# design.net
KiCad netlist of a schematic drawn in Altium Designer
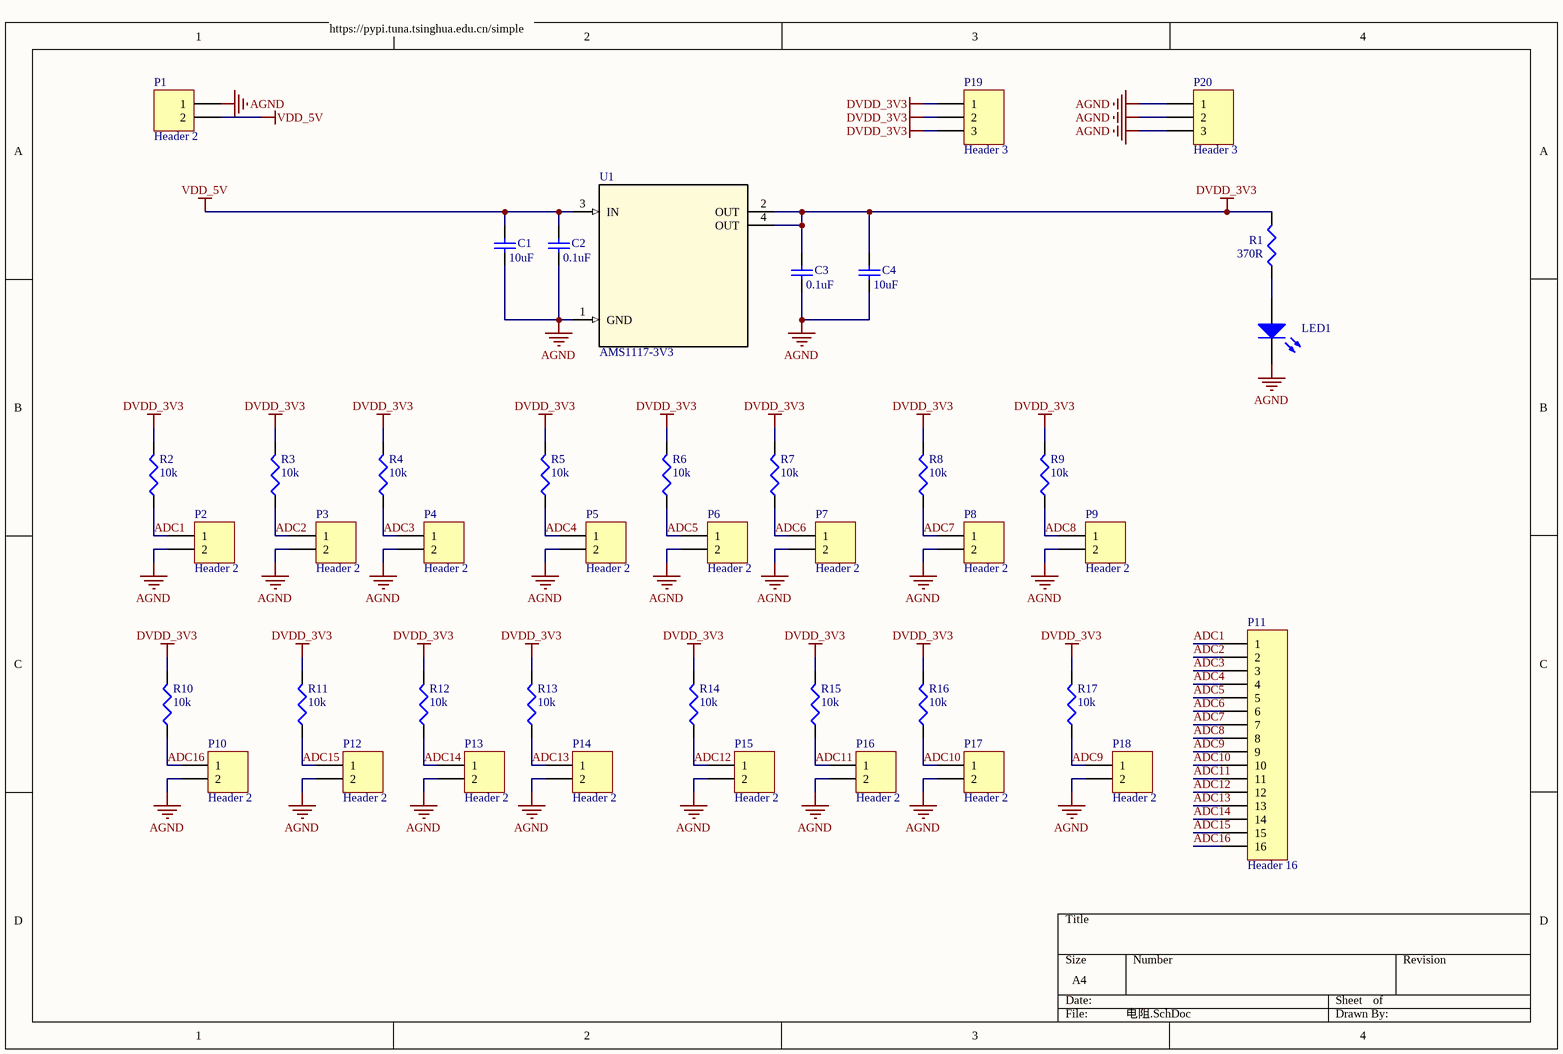
[diagram p0: 电阻.SchDoc]

(export (version "E")
  (design (tool "Eeschema 10.0.6"))
  (components
    (comp (ref "C1")
      (value "10uF")
      (footprint "C-0603")
      (description "Capacitor (Semiconductor SIM Model)")
      (fields (field (name "PUBLISHER") "Altium Limited"))
      (libsource (lib "Miscellaneous Devices") (part "Cap Semi"))
    )
    (comp (ref "C2")
      (value "0.1uF")
      (footprint "C-0603")
      (description "Capacitor (Semiconductor SIM Model)")
      (fields (field (name "PUBLISHER") "Altium Limited"))
      (libsource (lib "Miscellaneous Devices") (part "Cap Semi"))
    )
    (comp (ref "C3")
      (value "0.1uF")
      (footprint "C-0603")
      (description "Capacitor (Semiconductor SIM Model)")
      (fields (field (name "PUBLISHER") "Altium Limited"))
      (libsource (lib "Miscellaneous Devices") (part "Cap Semi"))
    )
    (comp (ref "C4")
      (value "10uF")
      (footprint "C-0603")
      (description "Capacitor (Semiconductor SIM Model)")
      (fields (field (name "PUBLISHER") "Altium Limited"))
      (libsource (lib "Miscellaneous Devices") (part "Cap Semi"))
    )
    (comp (ref "LED1")
      (value "~")
      (footprint "CLED1608-0603")
      (description "Typical Chip LED")
      (fields (field (name "PUBLISHER") "Altium Limited"))
      (libsource (lib "EButterflyIntegratedLibrary") (part "LED Chip"))
    )
    (comp (ref "P1")
      (value "Header 2")
      (footprint "XH2.54-LI-2P")
      (description "Header, 2-Pin")
      (fields (field (name "PUBLISHER") "Altium Limited"))
      (libsource (lib "") (part "Header 2_1"))
    )
    (comp (ref "P2")
      (value "Header 2")
      (footprint "XH2.0_2p")
      (description "Header, 2-Pin")
      (fields (field (name "PUBLISHER") "Altium Limited"))
      (libsource (lib "Miscellaneous Connectors") (part "Header 2"))
    )
    (comp (ref "P3")
      (value "Header 2")
      (footprint "XH2.0_2p")
      (description "Header, 2-Pin")
      (fields (field (name "PUBLISHER") "Altium Limited"))
      (libsource (lib "Miscellaneous Connectors") (part "Header 2"))
    )
    (comp (ref "P4")
      (value "Header 2")
      (footprint "XH2.0_2p")
      (description "Header, 2-Pin")
      (fields (field (name "PUBLISHER") "Altium Limited"))
      (libsource (lib "Miscellaneous Connectors") (part "Header 2"))
    )
    (comp (ref "P5")
      (value "Header 2")
      (footprint "XH2.0_2p")
      (description "Header, 2-Pin")
      (fields (field (name "PUBLISHER") "Altium Limited"))
      (libsource (lib "Miscellaneous Connectors") (part "Header 2"))
    )
    (comp (ref "P6")
      (value "Header 2")
      (footprint "XH2.0_2p")
      (description "Header, 2-Pin")
      (fields (field (name "PUBLISHER") "Altium Limited"))
      (libsource (lib "Miscellaneous Connectors") (part "Header 2"))
    )
    (comp (ref "P7")
      (value "Header 2")
      (footprint "XH2.0_2p")
      (description "Header, 2-Pin")
      (fields (field (name "PUBLISHER") "Altium Limited"))
      (libsource (lib "Miscellaneous Connectors") (part "Header 2"))
    )
    (comp (ref "P8")
      (value "Header 2")
      (footprint "XH2.0_2p")
      (description "Header, 2-Pin")
      (fields (field (name "PUBLISHER") "Altium Limited"))
      (libsource (lib "Miscellaneous Connectors") (part "Header 2"))
    )
    (comp (ref "P9")
      (value "Header 2")
      (footprint "XH2.0_2p")
      (description "Header, 2-Pin")
      (fields (field (name "PUBLISHER") "Altium Limited"))
      (libsource (lib "Miscellaneous Connectors") (part "Header 2"))
    )
    (comp (ref "P10")
      (value "Header 2")
      (footprint "XH2.0_2p")
      (description "Header, 2-Pin")
      (fields (field (name "PUBLISHER") "Altium Limited"))
      (libsource (lib "Miscellaneous Connectors") (part "Header 2"))
    )
    (comp (ref "P11")
      (value "Header 16")
      (footprint "HDR1X16")
      (description "Header, 16-Pin")
      (fields (field (name "PUBLISHER") "Altium Limited"))
      (libsource (lib "Miscellaneous Connectors") (part "Header 16"))
    )
    (comp (ref "P12")
      (value "Header 2")
      (footprint "XH2.0_2p")
      (description "Header, 2-Pin")
      (fields (field (name "PUBLISHER") "Altium Limited"))
      (libsource (lib "Miscellaneous Connectors") (part "Header 2"))
    )
    (comp (ref "P13")
      (value "Header 2")
      (footprint "XH2.0_2p")
      (description "Header, 2-Pin")
      (fields (field (name "PUBLISHER") "Altium Limited"))
      (libsource (lib "Miscellaneous Connectors") (part "Header 2"))
    )
    (comp (ref "P14")
      (value "Header 2")
      (footprint "XH2.0_2p")
      (description "Header, 2-Pin")
      (fields (field (name "PUBLISHER") "Altium Limited"))
      (libsource (lib "Miscellaneous Connectors") (part "Header 2"))
    )
    (comp (ref "P15")
      (value "Header 2")
      (footprint "XH2.0_2p")
      (description "Header, 2-Pin")
      (fields (field (name "PUBLISHER") "Altium Limited"))
      (libsource (lib "Miscellaneous Connectors") (part "Header 2"))
    )
    (comp (ref "P16")
      (value "Header 2")
      (footprint "XH2.0_2p")
      (description "Header, 2-Pin")
      (fields (field (name "PUBLISHER") "Altium Limited"))
      (libsource (lib "Miscellaneous Connectors") (part "Header 2"))
    )
    (comp (ref "P17")
      (value "Header 2")
      (footprint "XH2.0_2p")
      (description "Header, 2-Pin")
      (fields (field (name "PUBLISHER") "Altium Limited"))
      (libsource (lib "Miscellaneous Connectors") (part "Header 2"))
    )
    (comp (ref "P18")
      (value "Header 2")
      (footprint "XH2.0_2p")
      (description "Header, 2-Pin")
      (fields (field (name "PUBLISHER") "Altium Limited"))
      (libsource (lib "Miscellaneous Connectors") (part "Header 2"))
    )
    (comp (ref "P19")
      (value "Header 3")
      (footprint "HDR1X3")
      (description "Header, 3-Pin")
      (fields (field (name "PUBLISHER") "Altium Limited"))
      (libsource (lib "Miscellaneous Connectors") (part "Header 3"))
    )
    (comp (ref "P20")
      (value "Header 3")
      (footprint "HDR1X3")
      (description "Header, 3-Pin")
      (fields (field (name "PUBLISHER") "Altium Limited"))
      (libsource (lib "Miscellaneous Connectors") (part "Header 3"))
    )
    (comp (ref "R1")
      (value "370R")
      (footprint "R-0603")
      (description "Resistor")
      (fields (field (name "Comment") "Res3") (field (name "PUBLISHER") "Altium Limited"))
      (libsource (lib "Miscellaneous Devices") (part "Res3"))
    )
    (comp (ref "R2")
      (value "10k")
      (footprint "R-0603")
      (description "Resistor")
      (fields (field (name "Comment") "Res3") (field (name "PUBLISHER") "Altium Limited"))
      (libsource (lib "Miscellaneous Devices") (part "Res3"))
    )
    (comp (ref "R3")
      (value "10k")
      (footprint "R-0603")
      (description "Resistor")
      (fields (field (name "Comment") "Res3") (field (name "PUBLISHER") "Altium Limited"))
      (libsource (lib "Miscellaneous Devices") (part "Res3"))
    )
    (comp (ref "R4")
      (value "10k")
      (footprint "R-0603")
      (description "Resistor")
      (fields (field (name "Comment") "Res3") (field (name "PUBLISHER") "Altium Limited"))
      (libsource (lib "Miscellaneous Devices") (part "Res3"))
    )
    (comp (ref "R5")
      (value "10k")
      (footprint "R-0603")
      (description "Resistor")
      (fields (field (name "Comment") "Res3") (field (name "PUBLISHER") "Altium Limited"))
      (libsource (lib "Miscellaneous Devices") (part "Res3"))
    )
    (comp (ref "R6")
      (value "10k")
      (footprint "R-0603")
      (description "Resistor")
      (fields (field (name "Comment") "Res3") (field (name "PUBLISHER") "Altium Limited"))
      (libsource (lib "Miscellaneous Devices") (part "Res3"))
    )
    (comp (ref "R7")
      (value "10k")
      (footprint "R-0603")
      (description "Resistor")
      (fields (field (name "Comment") "Res3") (field (name "PUBLISHER") "Altium Limited"))
      (libsource (lib "Miscellaneous Devices") (part "Res3"))
    )
    (comp (ref "R8")
      (value "10k")
      (footprint "R-0603")
      (description "Resistor")
      (fields (field (name "Comment") "Res3") (field (name "PUBLISHER") "Altium Limited"))
      (libsource (lib "Miscellaneous Devices") (part "Res3"))
    )
    (comp (ref "R9")
      (value "10k")
      (footprint "R-0603")
      (description "Resistor")
      (fields (field (name "Comment") "Res3") (field (name "PUBLISHER") "Altium Limited"))
      (libsource (lib "Miscellaneous Devices") (part "Res3"))
    )
    (comp (ref "R10")
      (value "10k")
      (footprint "R-0603")
      (description "Resistor")
      (fields (field (name "Comment") "Res3") (field (name "PUBLISHER") "Altium Limited"))
      (libsource (lib "Miscellaneous Devices") (part "Res3"))
    )
    (comp (ref "R11")
      (value "10k")
      (footprint "R-0603")
      (description "Resistor")
      (fields (field (name "Comment") "Res3") (field (name "PUBLISHER") "Altium Limited"))
      (libsource (lib "Miscellaneous Devices") (part "Res3"))
    )
    (comp (ref "R12")
      (value "10k")
      (footprint "R-0603")
      (description "Resistor")
      (fields (field (name "Comment") "Res3") (field (name "PUBLISHER") "Altium Limited"))
      (libsource (lib "Miscellaneous Devices") (part "Res3"))
    )
    (comp (ref "R13")
      (value "10k")
      (footprint "R-0603")
      (description "Resistor")
      (fields (field (name "Comment") "Res3") (field (name "PUBLISHER") "Altium Limited"))
      (libsource (lib "Miscellaneous Devices") (part "Res3"))
    )
    (comp (ref "R14")
      (value "10k")
      (footprint "R-0603")
      (description "Resistor")
      (fields (field (name "Comment") "Res3") (field (name "PUBLISHER") "Altium Limited"))
      (libsource (lib "Miscellaneous Devices") (part "Res3"))
    )
    (comp (ref "R15")
      (value "10k")
      (footprint "R-0603")
      (description "Resistor")
      (fields (field (name "Comment") "Res3") (field (name "PUBLISHER") "Altium Limited"))
      (libsource (lib "Miscellaneous Devices") (part "Res3"))
    )
    (comp (ref "R16")
      (value "10k")
      (footprint "R-0603")
      (description "Resistor")
      (fields (field (name "Comment") "Res3") (field (name "PUBLISHER") "Altium Limited"))
      (libsource (lib "Miscellaneous Devices") (part "Res3"))
    )
    (comp (ref "R17")
      (value "10k")
      (footprint "R-0603")
      (description "Resistor")
      (fields (field (name "Comment") "Res3") (field (name "PUBLISHER") "Altium Limited"))
      (libsource (lib "Miscellaneous Devices") (part "Res3"))
    )
    (comp (ref "U1")
      (value "AMS1117-3V3")
      (footprint "LM317")
      (description "LM317DCYR-SOT223")
      (fields
        (field (name "PARTNUMBER") "LM317DCYR")
        (field (name "ALTERNATE_PARTNUMBER") "LM317DCY")
        (field (name "SYMBOLCREATER") "Altium")
      )
      (libsource (lib "LM317") (part "LM317DCYR"))
    )
  )
  (nets
    (net (code "1") (name "/ADC1") (class "Default")
      (node (ref "P11") (pin "1") (pinfunction "1_1") (pintype "passive"))
      (node (ref "P2") (pin "1") (pinfunction "1_1") (pintype "passive"))
      (node (ref "R2") (pin "1") (pinfunction "1_1") (pintype "passive"))
    )
    (net (code "2") (name "/ADC2") (class "Default")
      (node (ref "P11") (pin "2") (pinfunction "2_2") (pintype "passive"))
      (node (ref "P3") (pin "1") (pinfunction "1_1") (pintype "passive"))
      (node (ref "R3") (pin "1") (pinfunction "1_1") (pintype "passive"))
    )
    (net (code "3") (name "/ADC3") (class "Default")
      (node (ref "P11") (pin "3") (pinfunction "3_3") (pintype "passive"))
      (node (ref "P4") (pin "1") (pinfunction "1_1") (pintype "passive"))
      (node (ref "R4") (pin "1") (pinfunction "1_1") (pintype "passive"))
    )
    (net (code "4") (name "/ADC4") (class "Default")
      (node (ref "P11") (pin "4") (pinfunction "4_4") (pintype "passive"))
      (node (ref "P5") (pin "1") (pinfunction "1_1") (pintype "passive"))
      (node (ref "R5") (pin "1") (pinfunction "1_1") (pintype "passive"))
    )
    (net (code "5") (name "/ADC5") (class "Default")
      (node (ref "P11") (pin "5") (pinfunction "5_5") (pintype "passive"))
      (node (ref "P6") (pin "1") (pinfunction "1_1") (pintype "passive"))
      (node (ref "R6") (pin "1") (pinfunction "1_1") (pintype "passive"))
    )
    (net (code "6") (name "/ADC6") (class "Default")
      (node (ref "P11") (pin "6") (pinfunction "6_6") (pintype "passive"))
      (node (ref "P7") (pin "1") (pinfunction "1_1") (pintype "passive"))
      (node (ref "R7") (pin "1") (pinfunction "1_1") (pintype "passive"))
    )
    (net (code "7") (name "/ADC7") (class "Default")
      (node (ref "P11") (pin "7") (pinfunction "7_7") (pintype "passive"))
      (node (ref "P8") (pin "1") (pinfunction "1_1") (pintype "passive"))
      (node (ref "R8") (pin "1") (pinfunction "1_1") (pintype "passive"))
    )
    (net (code "8") (name "/ADC8") (class "Default")
      (node (ref "P11") (pin "8") (pinfunction "8_8") (pintype "passive"))
      (node (ref "P9") (pin "1") (pinfunction "1_1") (pintype "passive"))
      (node (ref "R9") (pin "1") (pinfunction "1_1") (pintype "passive"))
    )
    (net (code "9") (name "/ADC9") (class "Default")
      (node (ref "P11") (pin "9") (pinfunction "9_9") (pintype "passive"))
      (node (ref "P18") (pin "1") (pinfunction "1_1") (pintype "passive"))
      (node (ref "R17") (pin "1") (pinfunction "1_1") (pintype "passive"))
    )
    (net (code "10") (name "/ADC10") (class "Default")
      (node (ref "P11") (pin "10") (pinfunction "10_10") (pintype "passive"))
      (node (ref "P17") (pin "1") (pinfunction "1_1") (pintype "passive"))
      (node (ref "R16") (pin "1") (pinfunction "1_1") (pintype "passive"))
    )
    (net (code "11") (name "/ADC11") (class "Default")
      (node (ref "P11") (pin "11") (pinfunction "11_11") (pintype "passive"))
      (node (ref "P16") (pin "1") (pinfunction "1_1") (pintype "passive"))
      (node (ref "R15") (pin "1") (pinfunction "1_1") (pintype "passive"))
    )
    (net (code "12") (name "/ADC12") (class "Default")
      (node (ref "P11") (pin "12") (pinfunction "12_12") (pintype "passive"))
      (node (ref "P15") (pin "1") (pinfunction "1_1") (pintype "passive"))
      (node (ref "R14") (pin "1") (pinfunction "1_1") (pintype "passive"))
    )
    (net (code "13") (name "/ADC13") (class "Default")
      (node (ref "P11") (pin "13") (pinfunction "13_13") (pintype "passive"))
      (node (ref "P14") (pin "1") (pinfunction "1_1") (pintype "passive"))
      (node (ref "R13") (pin "1") (pinfunction "1_1") (pintype "passive"))
    )
    (net (code "14") (name "/ADC14") (class "Default")
      (node (ref "P11") (pin "14") (pinfunction "14_14") (pintype "passive"))
      (node (ref "P13") (pin "1") (pinfunction "1_1") (pintype "passive"))
      (node (ref "R12") (pin "1") (pinfunction "1_1") (pintype "passive"))
    )
    (net (code "15") (name "/ADC15") (class "Default")
      (node (ref "P11") (pin "15") (pinfunction "15_15") (pintype "passive"))
      (node (ref "P12") (pin "1") (pinfunction "1_1") (pintype "passive"))
      (node (ref "R11") (pin "1") (pinfunction "1_1") (pintype "passive"))
    )
    (net (code "16") (name "/ADC16") (class "Default")
      (node (ref "P10") (pin "1") (pinfunction "1_1") (pintype "passive"))
      (node (ref "P11") (pin "16") (pinfunction "16_16") (pintype "passive"))
      (node (ref "R10") (pin "1") (pinfunction "1_1") (pintype "passive"))
    )
    (net (code "17") (name "AGND") (class "Default")
      (node (ref "C1") (pin "1") (pinfunction "1_1") (pintype "passive"))
      (node (ref "C2") (pin "1") (pinfunction "1_1") (pintype "passive"))
      (node (ref "C3") (pin "1") (pinfunction "1_1") (pintype "passive"))
      (node (ref "C4") (pin "1") (pinfunction "1_1") (pintype "passive"))
      (node (ref "LED1") (pin "2") (pinfunction "K_2") (pintype "passive"))
      (node (ref "P1") (pin "1") (pinfunction "1_1") (pintype "passive"))
      (node (ref "P10") (pin "2") (pinfunction "2_2") (pintype "passive"))
      (node (ref "P12") (pin "2") (pinfunction "2_2") (pintype "passive"))
      (node (ref "P13") (pin "2") (pinfunction "2_2") (pintype "passive"))
      (node (ref "P14") (pin "2") (pinfunction "2_2") (pintype "passive"))
      (node (ref "P15") (pin "2") (pinfunction "2_2") (pintype "passive"))
      (node (ref "P16") (pin "2") (pinfunction "2_2") (pintype "passive"))
      (node (ref "P17") (pin "2") (pinfunction "2_2") (pintype "passive"))
      (node (ref "P18") (pin "2") (pinfunction "2_2") (pintype "passive"))
      (node (ref "P2") (pin "2") (pinfunction "2_2") (pintype "passive"))
      (node (ref "P20") (pin "1") (pinfunction "1_1") (pintype "passive"))
      (node (ref "P20") (pin "2") (pinfunction "2_2") (pintype "passive"))
      (node (ref "P20") (pin "3") (pinfunction "3_3") (pintype "passive"))
      (node (ref "P3") (pin "2") (pinfunction "2_2") (pintype "passive"))
      (node (ref "P4") (pin "2") (pinfunction "2_2") (pintype "passive"))
      (node (ref "P5") (pin "2") (pinfunction "2_2") (pintype "passive"))
      (node (ref "P6") (pin "2") (pinfunction "2_2") (pintype "passive"))
      (node (ref "P7") (pin "2") (pinfunction "2_2") (pintype "passive"))
      (node (ref "P8") (pin "2") (pinfunction "2_2") (pintype "passive"))
      (node (ref "P9") (pin "2") (pinfunction "2_2") (pintype "passive"))
      (node (ref "U1") (pin "1") (pinfunction "GND_1") (pintype "input"))
    )
    (net (code "18") (name "DVDD_3V3") (class "Default")
      (node (ref "C3") (pin "2") (pinfunction "2_2") (pintype "passive"))
      (node (ref "C4") (pin "2") (pinfunction "2_2") (pintype "passive"))
      (node (ref "P19") (pin "1") (pinfunction "1_1") (pintype "passive"))
      (node (ref "P19") (pin "2") (pinfunction "2_2") (pintype "passive"))
      (node (ref "P19") (pin "3") (pinfunction "3_3") (pintype "passive"))
      (node (ref "R1") (pin "2") (pinfunction "2_2") (pintype "passive"))
      (node (ref "R10") (pin "2") (pinfunction "2_2") (pintype "passive"))
      (node (ref "R11") (pin "2") (pinfunction "2_2") (pintype "passive"))
      (node (ref "R12") (pin "2") (pinfunction "2_2") (pintype "passive"))
      (node (ref "R13") (pin "2") (pinfunction "2_2") (pintype "passive"))
      (node (ref "R14") (pin "2") (pinfunction "2_2") (pintype "passive"))
      (node (ref "R15") (pin "2") (pinfunction "2_2") (pintype "passive"))
      (node (ref "R16") (pin "2") (pinfunction "2_2") (pintype "passive"))
      (node (ref "R17") (pin "2") (pinfunction "2_2") (pintype "passive"))
      (node (ref "R2") (pin "2") (pinfunction "2_2") (pintype "passive"))
      (node (ref "R3") (pin "2") (pinfunction "2_2") (pintype "passive"))
      (node (ref "R4") (pin "2") (pinfunction "2_2") (pintype "passive"))
      (node (ref "R5") (pin "2") (pinfunction "2_2") (pintype "passive"))
      (node (ref "R6") (pin "2") (pinfunction "2_2") (pintype "passive"))
      (node (ref "R7") (pin "2") (pinfunction "2_2") (pintype "passive"))
      (node (ref "R8") (pin "2") (pinfunction "2_2") (pintype "passive"))
      (node (ref "R9") (pin "2") (pinfunction "2_2") (pintype "passive"))
      (node (ref "U1") (pin "2") (pinfunction "OUT_2") (pintype "passive"))
      (node (ref "U1") (pin "4") (pinfunction "OUT_4") (pintype "passive"))
    )
    (net (code "19") (name "Net-(LED1-A)") (class "Default")
      (node (ref "LED1") (pin "1") (pinfunction "A_1") (pintype "passive"))
      (node (ref "R1") (pin "1") (pinfunction "1_1") (pintype "passive"))
    )
    (net (code "20") (name "VDD_5V") (class "Default")
      (node (ref "C1") (pin "2") (pinfunction "2_2") (pintype "passive"))
      (node (ref "C2") (pin "2") (pinfunction "2_2") (pintype "passive"))
      (node (ref "P1") (pin "2") (pinfunction "2_2") (pintype "passive"))
      (node (ref "U1") (pin "3") (pinfunction "IN_3") (pintype "input"))
    )
  )
)
